# LevelShifter.net
KiCad netlist of a schematic drawn in EAGLE
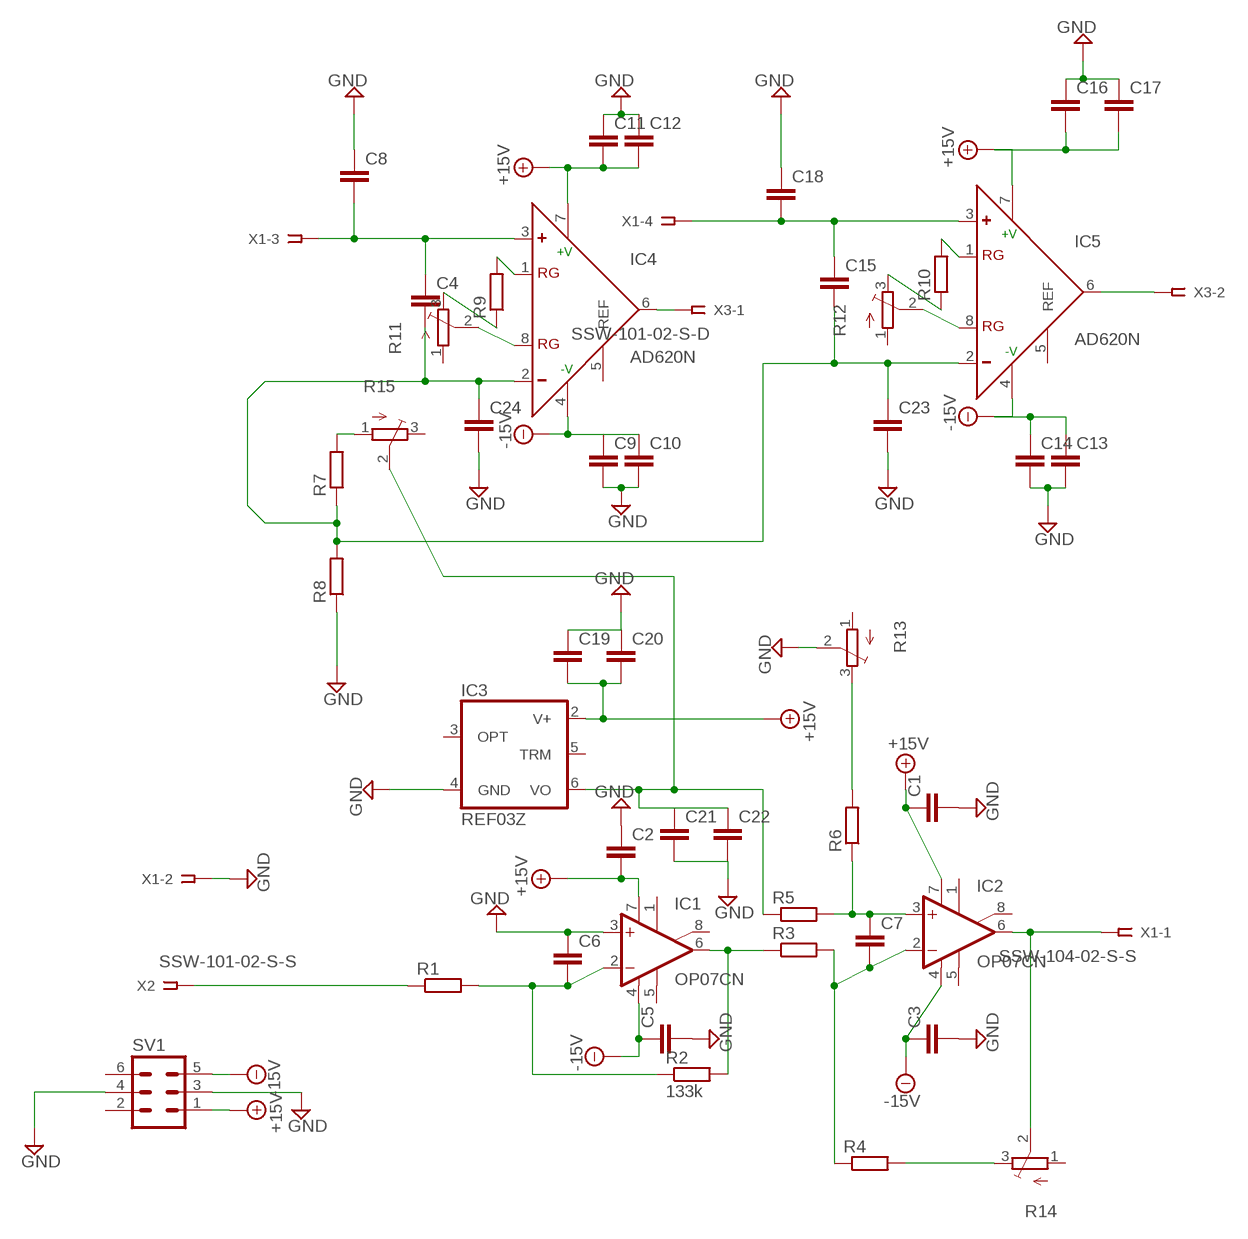
[diagram p0: schematic, sheet 1]

(export (version "E")
  (design (tool "Eeschema 10.0.6"))
  (components
    (comp (ref "C1")
      (value "C-EUC0805")
      (footprint "eagle-import:C0805")
      (libsource (lib "eagle-import") (part "C-EUC0805"))
    )
    (comp (ref "C2")
      (value "C-EUC0805")
      (footprint "eagle-import:C0805")
      (libsource (lib "eagle-import") (part "C-EUC0805"))
    )
    (comp (ref "C3")
      (value "C-EUC0805")
      (footprint "eagle-import:C0805")
      (libsource (lib "eagle-import") (part "C-EUC0805"))
    )
    (comp (ref "C4")
      (value "C-EUC0805")
      (footprint "eagle-import:C0805")
      (libsource (lib "eagle-import") (part "C-EUC0805"))
    )
    (comp (ref "C5")
      (value "C-EUC0805")
      (footprint "eagle-import:C0805")
      (libsource (lib "eagle-import") (part "C-EUC0805"))
    )
    (comp (ref "C6")
      (value "C-EUC0805")
      (footprint "eagle-import:C0805")
      (libsource (lib "eagle-import") (part "C-EUC0805"))
    )
    (comp (ref "C7")
      (value "C-EUC0805")
      (footprint "eagle-import:C0805")
      (libsource (lib "eagle-import") (part "C-EUC0805"))
    )
    (comp (ref "C8")
      (value "C-EUC0805")
      (footprint "eagle-import:C0805")
      (libsource (lib "eagle-import") (part "C-EUC0805"))
    )
    (comp (ref "C9")
      (value "C-EUC0805")
      (footprint "eagle-import:C0805")
      (libsource (lib "eagle-import") (part "C-EUC0805"))
    )
    (comp (ref "C10")
      (value "C-EUC0805")
      (footprint "eagle-import:C0805")
      (libsource (lib "eagle-import") (part "C-EUC0805"))
    )
    (comp (ref "C11")
      (value "C-EUC0805")
      (footprint "eagle-import:C0805")
      (libsource (lib "eagle-import") (part "C-EUC0805"))
    )
    (comp (ref "C12")
      (value "C-EUC0805")
      (footprint "eagle-import:C0805")
      (libsource (lib "eagle-import") (part "C-EUC0805"))
    )
    (comp (ref "C13")
      (value "C-EUC0805")
      (footprint "eagle-import:C0805")
      (libsource (lib "eagle-import") (part "C-EUC0805"))
    )
    (comp (ref "C14")
      (value "C-EUC0805")
      (footprint "eagle-import:C0805")
      (libsource (lib "eagle-import") (part "C-EUC0805"))
    )
    (comp (ref "C15")
      (value "C-EUC0805")
      (footprint "eagle-import:C0805")
      (libsource (lib "eagle-import") (part "C-EUC0805"))
    )
    (comp (ref "C16")
      (value "C-EUC0805")
      (footprint "eagle-import:C0805")
      (libsource (lib "eagle-import") (part "C-EUC0805"))
    )
    (comp (ref "C17")
      (value "C-EUC0805")
      (footprint "eagle-import:C0805")
      (libsource (lib "eagle-import") (part "C-EUC0805"))
    )
    (comp (ref "C18")
      (value "C-EUC0805")
      (footprint "eagle-import:C0805")
      (libsource (lib "eagle-import") (part "C-EUC0805"))
    )
    (comp (ref "C19")
      (value "C-EUC0805")
      (footprint "eagle-import:C0805")
      (libsource (lib "eagle-import") (part "C-EUC0805"))
    )
    (comp (ref "C20")
      (value "C-EUC0805")
      (footprint "eagle-import:C0805")
      (libsource (lib "eagle-import") (part "C-EUC0805"))
    )
    (comp (ref "C21")
      (value "C-EUC0805")
      (footprint "eagle-import:C0805")
      (libsource (lib "eagle-import") (part "C-EUC0805"))
    )
    (comp (ref "C22")
      (value "C-EUC0805")
      (footprint "eagle-import:C0805")
      (libsource (lib "eagle-import") (part "C-EUC0805"))
    )
    (comp (ref "C23")
      (value "C-EUC0805")
      (footprint "eagle-import:C0805")
      (libsource (lib "eagle-import") (part "C-EUC0805"))
    )
    (comp (ref "C24")
      (value "C-EUC0805")
      (footprint "eagle-import:C0805")
      (libsource (lib "eagle-import") (part "C-EUC0805"))
    )
    (comp (ref "IC1")
      (value "OP07CN")
      (footprint "eagle-import:DIL08")
      (libsource (lib "eagle-import") (part "OP07NC"))
    )
    (comp (ref "IC2")
      (value "OP07CN")
      (footprint "eagle-import:DIL08")
      (libsource (lib "eagle-import") (part "OP07NC"))
    )
    (comp (ref "IC3")
      (value "REF03Z")
      (footprint "eagle-import:DIL08")
      (libsource (lib "eagle-import") (part "REF03Z"))
    )
    (comp (ref "IC4")
      (value "AD620N")
      (footprint "eagle-import:DIL08")
      (fields (field (name "MF") "ALTERA CORPORATION") (field (name "MPN") "AD620AN"))
      (libsource (lib "eagle-import") (part "AD620N"))
    )
    (comp (ref "IC5")
      (value "AD620N")
      (footprint "eagle-import:DIL08")
      (fields (field (name "MF") "ALTERA CORPORATION") (field (name "MPN") "AD620AN"))
      (libsource (lib "eagle-import") (part "AD620N"))
    )
    (comp (ref "R1")
      (value "R-EU_R0805")
      (footprint "eagle-import:R0805")
      (libsource (lib "eagle-import") (part "R-EU_R0805"))
    )
    (comp (ref "R2")
      (value "133k")
      (footprint "eagle-import:R0805")
      (libsource (lib "eagle-import") (part "R-EU_R0805"))
    )
    (comp (ref "R3")
      (value "R-EU_R0805")
      (footprint "eagle-import:R0805")
      (libsource (lib "eagle-import") (part "R-EU_R0805"))
    )
    (comp (ref "R4")
      (value "R-EU_R0805")
      (footprint "eagle-import:R0805")
      (libsource (lib "eagle-import") (part "R-EU_R0805"))
    )
    (comp (ref "R5")
      (value "R-EU_R0805")
      (footprint "eagle-import:R0805")
      (libsource (lib "eagle-import") (part "R-EU_R0805"))
    )
    (comp (ref "R6")
      (value "R-EU_R0805")
      (footprint "eagle-import:R0805")
      (libsource (lib "eagle-import") (part "R-EU_R0805"))
    )
    (comp (ref "R7")
      (value "R-EU_R0805")
      (footprint "eagle-import:R0805")
      (libsource (lib "eagle-import") (part "R-EU_R0805"))
    )
    (comp (ref "R8")
      (value "R-EU_R0805")
      (footprint "eagle-import:R0805")
      (libsource (lib "eagle-import") (part "R-EU_R0805"))
    )
    (comp (ref "R9")
      (value "R-EU_R0805")
      (footprint "eagle-import:R0805")
      (libsource (lib "eagle-import") (part "R-EU_R0805"))
    )
    (comp (ref "R10")
      (value "R-EU_R0805")
      (footprint "eagle-import:R0805")
      (libsource (lib "eagle-import") (part "R-EU_R0805"))
    )
    (comp (ref "R11")
      (value "TRIM_EU-SM-42/43W")
      (footprint "eagle-import:SM-42_43W")
      (libsource (lib "eagle-import") (part "TRIM_EU-SM-42/43W"))
    )
    (comp (ref "R12")
      (value "TRIM_EU-SM-42/43W")
      (footprint "eagle-import:SM-42_43W")
      (libsource (lib "eagle-import") (part "TRIM_EU-SM-42/43W"))
    )
    (comp (ref "R13")
      (value "TRIM_EU-SM-42/43W")
      (footprint "eagle-import:SM-42_43W")
      (libsource (lib "eagle-import") (part "TRIM_EU-SM-42/43W"))
    )
    (comp (ref "R14")
      (value "TRIM_EU-SM-42/43W")
      (footprint "eagle-import:SM-42_43W")
      (libsource (lib "eagle-import") (part "TRIM_EU-SM-42/43W"))
    )
    (comp (ref "R15")
      (value "TRIM_EU-SM-42/43W")
      (footprint "eagle-import:SM-42_43W")
      (libsource (lib "eagle-import") (part "TRIM_EU-SM-42/43W"))
    )
    (comp (ref "SV1")
      (value "MA03-2")
      (footprint "eagle-import:MA03-2")
      (libsource (lib "eagle-import") (part "MA03-2"))
    )
    (comp (ref "X1")
      (value "SSW-104-02-S-S")
      (footprint "eagle-import:SSW-104-02-S-S")
      (libsource (lib "eagle-import") (part "SSW-104-02-S-S"))
    )
    (comp (ref "X2")
      (value "SSW-101-02-S-S")
      (footprint "eagle-import:SSW-101-02-S-S")
      (libsource (lib "eagle-import") (part "SSW-101-02-S-S"))
    )
    (comp (ref "X3")
      (value "SSW-101-02-S-D")
      (footprint "eagle-import:SSW-101-02-S-D")
      (libsource (lib "eagle-import") (part "SSW-101-02-S-D"))
    )
  )
  (nets
    (net (code "1") (name "+15V") (class "Default")
      (node (ref "C1") (pin "1") (pinfunction "1_1") (pintype "passive"))
      (node (ref "C11") (pin "2") (pinfunction "2_2") (pintype "passive"))
      (node (ref "C12") (pin "2") (pinfunction "2_2") (pintype "passive"))
      (node (ref "C16") (pin "2") (pinfunction "2_2") (pintype "passive"))
      (node (ref "C17") (pin "2") (pinfunction "2_2") (pintype "passive"))
      (node (ref "C19") (pin "2") (pinfunction "2_2") (pintype "passive"))
      (node (ref "C2") (pin "2") (pinfunction "2_2") (pintype "passive"))
      (node (ref "C20") (pin "2") (pinfunction "2_2") (pintype "passive"))
      (node (ref "IC1") (pin "7") (pinfunction "V+_7") (pintype "power_in"))
      (node (ref "IC2") (pin "7") (pinfunction "V+_7") (pintype "power_in"))
      (node (ref "IC3") (pin "2") (pinfunction "V+_2") (pintype "power_in"))
      (node (ref "IC4") (pin "7") (pinfunction "+V_7") (pintype "power_in"))
      (node (ref "IC5") (pin "7") (pinfunction "+V_7") (pintype "power_in"))
      (node (ref "SV1") (pin "1") (pinfunction "1_1") (pintype "passive"))
    )
    (net (code "2") (name "-15V") (class "Default")
      (node (ref "C10") (pin "1") (pinfunction "1_1") (pintype "passive"))
      (node (ref "C13") (pin "1") (pinfunction "1_1") (pintype "passive"))
      (node (ref "C14") (pin "1") (pinfunction "1_1") (pintype "passive"))
      (node (ref "C3") (pin "1") (pinfunction "1_1") (pintype "passive"))
      (node (ref "C5") (pin "1") (pinfunction "1_1") (pintype "passive"))
      (node (ref "C9") (pin "1") (pinfunction "1_1") (pintype "passive"))
      (node (ref "IC1") (pin "4") (pinfunction "V-_4") (pintype "power_in"))
      (node (ref "IC2") (pin "4") (pinfunction "V-_4") (pintype "power_in"))
      (node (ref "IC4") (pin "4") (pinfunction "-V_4") (pintype "power_in"))
      (node (ref "IC5") (pin "4") (pinfunction "-V_4") (pintype "power_in"))
      (node (ref "SV1") (pin "5") (pinfunction "5_5") (pintype "passive"))
    )
    (net (code "3") (name "GND") (class "Default")
      (node (ref "C1") (pin "2") (pinfunction "2_2") (pintype "passive"))
      (node (ref "C10") (pin "2") (pinfunction "2_2") (pintype "passive"))
      (node (ref "C11") (pin "1") (pinfunction "1_1") (pintype "passive"))
      (node (ref "C12") (pin "1") (pinfunction "1_1") (pintype "passive"))
      (node (ref "C13") (pin "2") (pinfunction "2_2") (pintype "passive"))
      (node (ref "C14") (pin "2") (pinfunction "2_2") (pintype "passive"))
      (node (ref "C16") (pin "1") (pinfunction "1_1") (pintype "passive"))
      (node (ref "C17") (pin "1") (pinfunction "1_1") (pintype "passive"))
      (node (ref "C18") (pin "1") (pinfunction "1_1") (pintype "passive"))
      (node (ref "C19") (pin "1") (pinfunction "1_1") (pintype "passive"))
      (node (ref "C2") (pin "1") (pinfunction "1_1") (pintype "passive"))
      (node (ref "C20") (pin "1") (pinfunction "1_1") (pintype "passive"))
      (node (ref "C21") (pin "2") (pinfunction "2_2") (pintype "passive"))
      (node (ref "C22") (pin "2") (pinfunction "2_2") (pintype "passive"))
      (node (ref "C23") (pin "2") (pinfunction "2_2") (pintype "passive"))
      (node (ref "C24") (pin "2") (pinfunction "2_2") (pintype "passive"))
      (node (ref "C3") (pin "2") (pinfunction "2_2") (pintype "passive"))
      (node (ref "C5") (pin "2") (pinfunction "2_2") (pintype "passive"))
      (node (ref "C6") (pin "1") (pinfunction "1_1") (pintype "passive"))
      (node (ref "C8") (pin "1") (pinfunction "1_1") (pintype "passive"))
      (node (ref "C9") (pin "2") (pinfunction "2_2") (pintype "passive"))
      (node (ref "IC1") (pin "3") (pinfunction "+IN_3") (pintype "input"))
      (node (ref "IC3") (pin "4") (pinfunction "GND_4") (pintype "power_in"))
      (node (ref "R13") (pin "2") (pinfunction "S_2") (pintype "passive"))
      (node (ref "R8") (pin "1") (pinfunction "1_1") (pintype "passive"))
      (node (ref "SV1") (pin "3") (pinfunction "3_3") (pintype "passive"))
      (node (ref "SV1") (pin "4") (pinfunction "4_4") (pintype "passive"))
      (node (ref "X1") (pin "2") (pinfunction "1_2") (pintype "passive"))
    )
    (net (code "4") (name "Net-(IC1--IN)") (class "Default")
      (node (ref "C6") (pin "2") (pinfunction "2_2") (pintype "passive"))
      (node (ref "IC1") (pin "2") (pinfunction "-IN_2") (pintype "input"))
      (node (ref "R1") (pin "2") (pinfunction "2_2") (pintype "passive"))
      (node (ref "R2") (pin "1") (pinfunction "1_1") (pintype "passive"))
    )
    (net (code "5") (name "Net-(IC1-OUT)") (class "Default")
      (node (ref "IC1") (pin "6") (pinfunction "OUT_6") (pintype "output"))
      (node (ref "R2") (pin "2") (pinfunction "2_2") (pintype "passive"))
      (node (ref "R3") (pin "1") (pinfunction "1_1") (pintype "passive"))
    )
    (net (code "6") (name "Net-(IC2-+IN)") (class "Default")
      (node (ref "C7") (pin "1") (pinfunction "1_1") (pintype "passive"))
      (node (ref "IC2") (pin "3") (pinfunction "+IN_3") (pintype "input"))
      (node (ref "R5") (pin "2") (pinfunction "2_2") (pintype "passive"))
      (node (ref "R6") (pin "1") (pinfunction "1_1") (pintype "passive"))
    )
    (net (code "7") (name "Net-(IC2--IN)") (class "Default")
      (node (ref "C7") (pin "2") (pinfunction "2_2") (pintype "passive"))
      (node (ref "IC2") (pin "2") (pinfunction "-IN_2") (pintype "input"))
      (node (ref "R3") (pin "2") (pinfunction "2_2") (pintype "passive"))
      (node (ref "R4") (pin "1") (pinfunction "1_1") (pintype "passive"))
    )
    (net (code "8") (name "Net-(IC2-OUT)") (class "Default")
      (node (ref "IC2") (pin "6") (pinfunction "OUT_6") (pintype "output"))
      (node (ref "R14") (pin "2") (pinfunction "S_2") (pintype "passive"))
      (node (ref "X1") (pin "1") (pinfunction "1_1") (pintype "passive"))
    )
    (net (code "9") (name "Net-(IC3-VO)") (class "Default")
      (node (ref "C21") (pin "1") (pinfunction "1_1") (pintype "passive"))
      (node (ref "C22") (pin "1") (pinfunction "1_1") (pintype "passive"))
      (node (ref "IC3") (pin "6") (pinfunction "VO_6") (pintype "output"))
      (node (ref "R15") (pin "2") (pinfunction "S_2") (pintype "passive"))
      (node (ref "R5") (pin "1") (pinfunction "1_1") (pintype "passive"))
    )
    (net (code "10") (name "Net-(IC4-+)") (class "Default")
      (node (ref "C4") (pin "1") (pinfunction "1_1") (pintype "passive"))
      (node (ref "C8") (pin "2") (pinfunction "2_2") (pintype "passive"))
      (node (ref "IC4") (pin "3") (pinfunction "+_3") (pintype "input"))
      (node (ref "X1") (pin "3") (pinfunction "1_3") (pintype "passive"))
    )
    (net (code "11") (name "Net-(IC4--)") (class "Default")
      (node (ref "C15") (pin "2") (pinfunction "2_2") (pintype "passive"))
      (node (ref "C23") (pin "1") (pinfunction "1_1") (pintype "passive"))
      (node (ref "C24") (pin "1") (pinfunction "1_1") (pintype "passive"))
      (node (ref "C4") (pin "2") (pinfunction "2_2") (pintype "passive"))
      (node (ref "IC4") (pin "2") (pinfunction "-_2") (pintype "input"))
      (node (ref "IC5") (pin "2") (pinfunction "-_2") (pintype "input"))
      (node (ref "R7") (pin "1") (pinfunction "1_1") (pintype "passive"))
      (node (ref "R8") (pin "2") (pinfunction "2_2") (pintype "passive"))
    )
    (net (code "12") (name "Net-(IC4-OUT)") (class "Default")
      (node (ref "IC4") (pin "6") (pinfunction "OUT_6") (pintype "output"))
      (node (ref "X3") (pin "1") (pinfunction "1_1") (pintype "passive"))
    )
    (net (code "13") (name "Net-(IC4-RG-Pad1)") (class "Default")
      (node (ref "IC4") (pin "1") (pinfunction "RG_1") (pintype "passive"))
      (node (ref "R9") (pin "2") (pinfunction "2_2") (pintype "passive"))
    )
    (net (code "14") (name "Net-(IC5-+)") (class "Default")
      (node (ref "C15") (pin "1") (pinfunction "1_1") (pintype "passive"))
      (node (ref "C18") (pin "2") (pinfunction "2_2") (pintype "passive"))
      (node (ref "IC5") (pin "3") (pinfunction "+_3") (pintype "input"))
      (node (ref "X1") (pin "4") (pinfunction "1_4") (pintype "passive"))
    )
    (net (code "15") (name "Net-(IC5-OUT)") (class "Default")
      (node (ref "IC5") (pin "6") (pinfunction "OUT_6") (pintype "output"))
      (node (ref "X3") (pin "2") (pinfunction "1_2") (pintype "passive"))
    )
    (net (code "16") (name "Net-(IC5-RG-Pad1)") (class "Default")
      (node (ref "IC5") (pin "1") (pinfunction "RG_1") (pintype "passive"))
      (node (ref "R10") (pin "2") (pinfunction "2_2") (pintype "passive"))
    )
    (net (code "17") (name "Net-(R1-Pad1)") (class "Default")
      (node (ref "R1") (pin "1") (pinfunction "1_1") (pintype "passive"))
      (node (ref "X2") (pin "1") (pinfunction "1_1") (pintype "passive"))
    )
    (net (code "18") (name "Net-(R11-E)") (class "Default")
      (node (ref "R11") (pin "3") (pinfunction "E_3") (pintype "passive"))
      (node (ref "R9") (pin "1") (pinfunction "1_1") (pintype "passive"))
    )
    (net (code "19") (name "Net-(R11-S)") (class "Default")
      (node (ref "IC4") (pin "8") (pinfunction "RG_8") (pintype "passive"))
      (node (ref "R11") (pin "2") (pinfunction "S_2") (pintype "passive"))
    )
    (net (code "20") (name "Net-(R12-E)") (class "Default")
      (node (ref "R10") (pin "1") (pinfunction "1_1") (pintype "passive"))
      (node (ref "R12") (pin "3") (pinfunction "E_3") (pintype "passive"))
    )
    (net (code "21") (name "Net-(R12-S)") (class "Default")
      (node (ref "IC5") (pin "8") (pinfunction "RG_8") (pintype "passive"))
      (node (ref "R12") (pin "2") (pinfunction "S_2") (pintype "passive"))
    )
    (net (code "22") (name "Net-(R13-E)") (class "Default")
      (node (ref "R13") (pin "3") (pinfunction "E_3") (pintype "passive"))
      (node (ref "R6") (pin "2") (pinfunction "2_2") (pintype "passive"))
    )
    (net (code "23") (name "Net-(R14-E)") (class "Default")
      (node (ref "R14") (pin "3") (pinfunction "E_3") (pintype "passive"))
      (node (ref "R4") (pin "2") (pinfunction "2_2") (pintype "passive"))
    )
    (net (code "24") (name "Net-(R15-A)") (class "Default")
      (node (ref "R15") (pin "1") (pinfunction "A_1") (pintype "passive"))
      (node (ref "R7") (pin "2") (pinfunction "2_2") (pintype "passive"))
    )
    (net (code "25") (name "unconnected-(IC1-ON1-Pad1)") (class "Default")
      (node (ref "IC1") (pin "1") (pinfunction "ON1_1") (pintype "passive"))
    )
    (net (code "26") (name "unconnected-(IC1-ON2-Pad8)") (class "Default")
      (node (ref "IC1") (pin "8") (pinfunction "ON2_8") (pintype "passive"))
    )
    (net (code "27") (name "unconnected-(IC1-OPT-Pad5)") (class "Default")
      (node (ref "IC1") (pin "5") (pinfunction "OPT_5") (pintype "passive"))
    )
    (net (code "28") (name "unconnected-(IC2-ON1-Pad1)") (class "Default")
      (node (ref "IC2") (pin "1") (pinfunction "ON1_1") (pintype "passive"))
    )
    (net (code "29") (name "unconnected-(IC2-ON2-Pad8)") (class "Default")
      (node (ref "IC2") (pin "8") (pinfunction "ON2_8") (pintype "passive"))
    )
    (net (code "30") (name "unconnected-(IC2-OPT-Pad5)") (class "Default")
      (node (ref "IC2") (pin "5") (pinfunction "OPT_5") (pintype "passive"))
    )
    (net (code "31") (name "unconnected-(IC3-OPT-Pad3)") (class "Default")
      (node (ref "IC3") (pin "3") (pinfunction "OPT_3") (pintype "output"))
    )
    (net (code "32") (name "unconnected-(IC3-TRM-Pad5)") (class "Default")
      (node (ref "IC3") (pin "5") (pinfunction "TRM_5") (pintype "input"))
    )
    (net (code "33") (name "unconnected-(IC4-REF-Pad5)") (class "Default")
      (node (ref "IC4") (pin "5") (pinfunction "REF_5") (pintype "passive"))
    )
    (net (code "34") (name "unconnected-(IC5-REF-Pad5)") (class "Default")
      (node (ref "IC5") (pin "5") (pinfunction "REF_5") (pintype "passive"))
    )
    (net (code "35") (name "unconnected-(R11-A-Pad1)") (class "Default")
      (node (ref "R11") (pin "1") (pinfunction "A_1") (pintype "passive"))
    )
    (net (code "36") (name "unconnected-(R12-A-Pad1)") (class "Default")
      (node (ref "R12") (pin "1") (pinfunction "A_1") (pintype "passive"))
    )
    (net (code "37") (name "unconnected-(R13-A-Pad1)") (class "Default")
      (node (ref "R13") (pin "1") (pinfunction "A_1") (pintype "passive"))
    )
    (net (code "38") (name "unconnected-(R14-A-Pad1)") (class "Default")
      (node (ref "R14") (pin "1") (pinfunction "A_1") (pintype "passive"))
    )
    (net (code "39") (name "unconnected-(R15-E-Pad3)") (class "Default")
      (node (ref "R15") (pin "3") (pinfunction "E_3") (pintype "passive"))
    )
    (net (code "40") (name "unconnected-(SV1-Pad2)") (class "Default")
      (node (ref "SV1") (pin "2") (pinfunction "2_2") (pintype "passive"))
    )
    (net (code "41") (name "unconnected-(SV1-Pad6)") (class "Default")
      (node (ref "SV1") (pin "6") (pinfunction "6_6") (pintype "passive"))
    )
  )
)
